# takahoot-controller.net
KiCad netlist of a schematic drawn in EAGLE
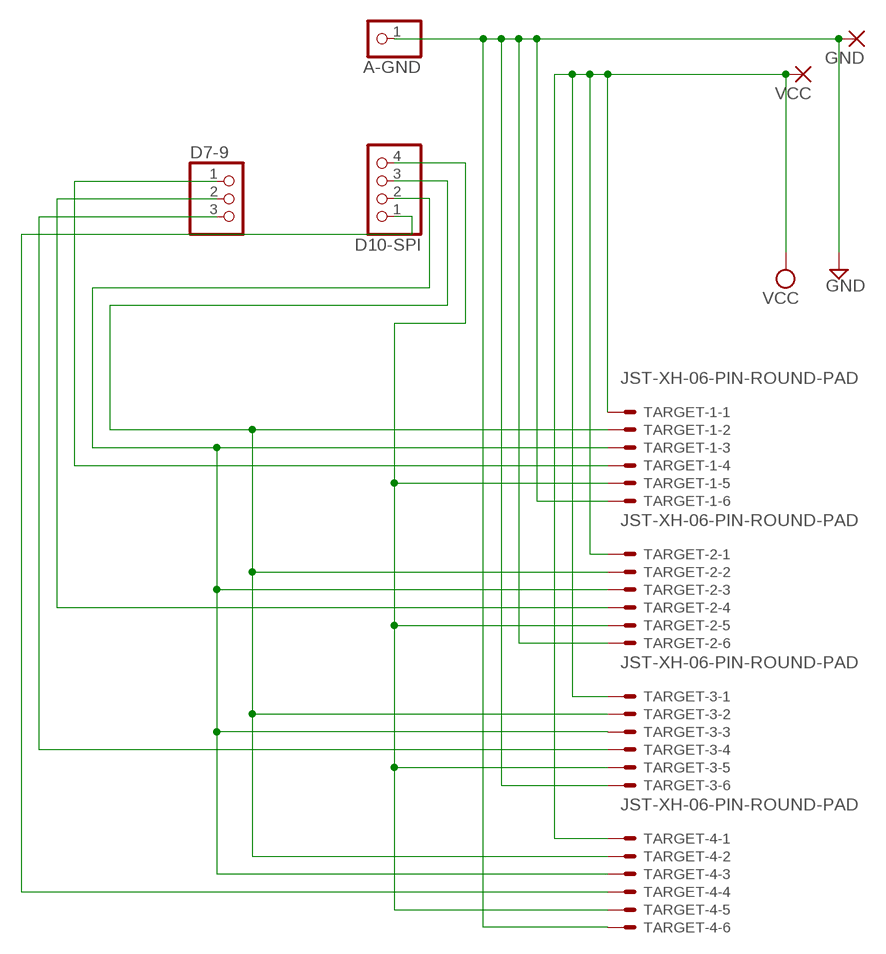
[diagram p0: schematic, sheet 1]

(export (version "E")
  (design (tool "Eeschema 10.0.6"))
  (components
    (comp (ref "A-GND")
      (value "PINHD-1X1")
      (footprint "eagle-import:1X01")
      (libsource (lib "eagle-import") (part "PINHD-1X1"))
    )
    (comp (ref "D7-9")
      (value "PINHD-1X3")
      (footprint "eagle-import:1X03")
      (libsource (lib "eagle-import") (part "PINHD-1X3"))
    )
    (comp (ref "D10-SPI")
      (value "PINHD-1X4")
      (footprint "eagle-import:1X04")
      (libsource (lib "eagle-import") (part "PINHD-1X4"))
    )
    (comp (ref "GND")
      (value "3,81/1,4")
      (footprint "eagle-import:3,81_1,4")
      (libsource (lib "eagle-import") (part "3,81/1,4"))
    )
    (comp (ref "TARGET-1")
      (value "JST-XH-06-PIN-ROUND-PAD")
      (footprint "eagle-import:JST-XH-06-PACKAGE-ROUND-PAD")
      (libsource (lib "eagle-import") (part "JST-XH-06-PIN-ROUND-PAD"))
    )
    (comp (ref "TARGET-2")
      (value "JST-XH-06-PIN-ROUND-PAD")
      (footprint "eagle-import:JST-XH-06-PACKAGE-ROUND-PAD")
      (libsource (lib "eagle-import") (part "JST-XH-06-PIN-ROUND-PAD"))
    )
    (comp (ref "TARGET-3")
      (value "JST-XH-06-PIN-ROUND-PAD")
      (footprint "eagle-import:JST-XH-06-PACKAGE-ROUND-PAD")
      (libsource (lib "eagle-import") (part "JST-XH-06-PIN-ROUND-PAD"))
    )
    (comp (ref "TARGET-4")
      (value "JST-XH-06-PIN-ROUND-PAD")
      (footprint "eagle-import:JST-XH-06-PACKAGE-ROUND-PAD")
      (libsource (lib "eagle-import") (part "JST-XH-06-PIN-ROUND-PAD"))
    )
    (comp (ref "VCC")
      (value "3,81/1,4")
      (footprint "eagle-import:3,81_1,4")
      (libsource (lib "eagle-import") (part "3,81/1,4"))
    )
  )
  (nets
    (net (code "1") (name "GND") (class "Default")
      (node (ref "A-GND") (pin "1") (pinfunction "1_1") (pintype "passive"))
      (node (ref "GND") (pin "1") (pinfunction "P_1") (pintype "passive"))
      (node (ref "TARGET-1") (pin "6") (pinfunction "S_6") (pintype "passive"))
      (node (ref "TARGET-2") (pin "6") (pinfunction "S_6") (pintype "passive"))
      (node (ref "TARGET-3") (pin "6") (pinfunction "S_6") (pintype "passive"))
      (node (ref "TARGET-4") (pin "6") (pinfunction "S_6") (pintype "passive"))
    )
    (net (code "2") (name "Net-(TARGET-1B-S)") (class "Default")
      (node (ref "D10-SPI") (pin "3") (pinfunction "3_3") (pintype "passive"))
      (node (ref "TARGET-1") (pin "2") (pinfunction "S_2") (pintype "passive"))
      (node (ref "TARGET-2") (pin "2") (pinfunction "S_2") (pintype "passive"))
      (node (ref "TARGET-3") (pin "2") (pinfunction "S_2") (pintype "passive"))
      (node (ref "TARGET-4") (pin "2") (pinfunction "S_2") (pintype "passive"))
    )
    (net (code "3") (name "Net-(TARGET-1C-S)") (class "Default")
      (node (ref "D10-SPI") (pin "2") (pinfunction "2_2") (pintype "passive"))
      (node (ref "TARGET-1") (pin "3") (pinfunction "S_3") (pintype "passive"))
      (node (ref "TARGET-2") (pin "3") (pinfunction "S_3") (pintype "passive"))
      (node (ref "TARGET-3") (pin "3") (pinfunction "S_3") (pintype "passive"))
      (node (ref "TARGET-4") (pin "3") (pinfunction "S_3") (pintype "passive"))
    )
    (net (code "4") (name "Net-(TARGET-1D-S)") (class "Default")
      (node (ref "D7-9") (pin "1") (pinfunction "1_1") (pintype "passive"))
      (node (ref "TARGET-1") (pin "4") (pinfunction "S_4") (pintype "passive"))
    )
    (net (code "5") (name "Net-(TARGET-1E-S)") (class "Default")
      (node (ref "D10-SPI") (pin "4") (pinfunction "4_4") (pintype "passive"))
      (node (ref "TARGET-1") (pin "5") (pinfunction "S_5") (pintype "passive"))
      (node (ref "TARGET-2") (pin "5") (pinfunction "S_5") (pintype "passive"))
      (node (ref "TARGET-3") (pin "5") (pinfunction "S_5") (pintype "passive"))
      (node (ref "TARGET-4") (pin "5") (pinfunction "S_5") (pintype "passive"))
    )
    (net (code "6") (name "Net-(TARGET-2D-S)") (class "Default")
      (node (ref "D7-9") (pin "2") (pinfunction "2_2") (pintype "passive"))
      (node (ref "TARGET-2") (pin "4") (pinfunction "S_4") (pintype "passive"))
    )
    (net (code "7") (name "Net-(TARGET-3D-S)") (class "Default")
      (node (ref "D7-9") (pin "3") (pinfunction "3_3") (pintype "passive"))
      (node (ref "TARGET-3") (pin "4") (pinfunction "S_4") (pintype "passive"))
    )
    (net (code "8") (name "Net-(TARGET-4D-S)") (class "Default")
      (node (ref "D10-SPI") (pin "1") (pinfunction "1_1") (pintype "passive"))
      (node (ref "TARGET-4") (pin "4") (pinfunction "S_4") (pintype "passive"))
    )
    (net (code "9") (name "VCC") (class "Default")
      (node (ref "TARGET-1") (pin "1") (pinfunction "S_1") (pintype "passive"))
      (node (ref "TARGET-2") (pin "1") (pinfunction "S_1") (pintype "passive"))
      (node (ref "TARGET-3") (pin "1") (pinfunction "S_1") (pintype "passive"))
      (node (ref "TARGET-4") (pin "1") (pinfunction "S_1") (pintype "passive"))
      (node (ref "VCC") (pin "1") (pinfunction "P_1") (pintype "passive"))
    )
  )
)
